# MCU_144_IOs_Clone.net
KiCad netlist of a schematic drawn in Altium Designer
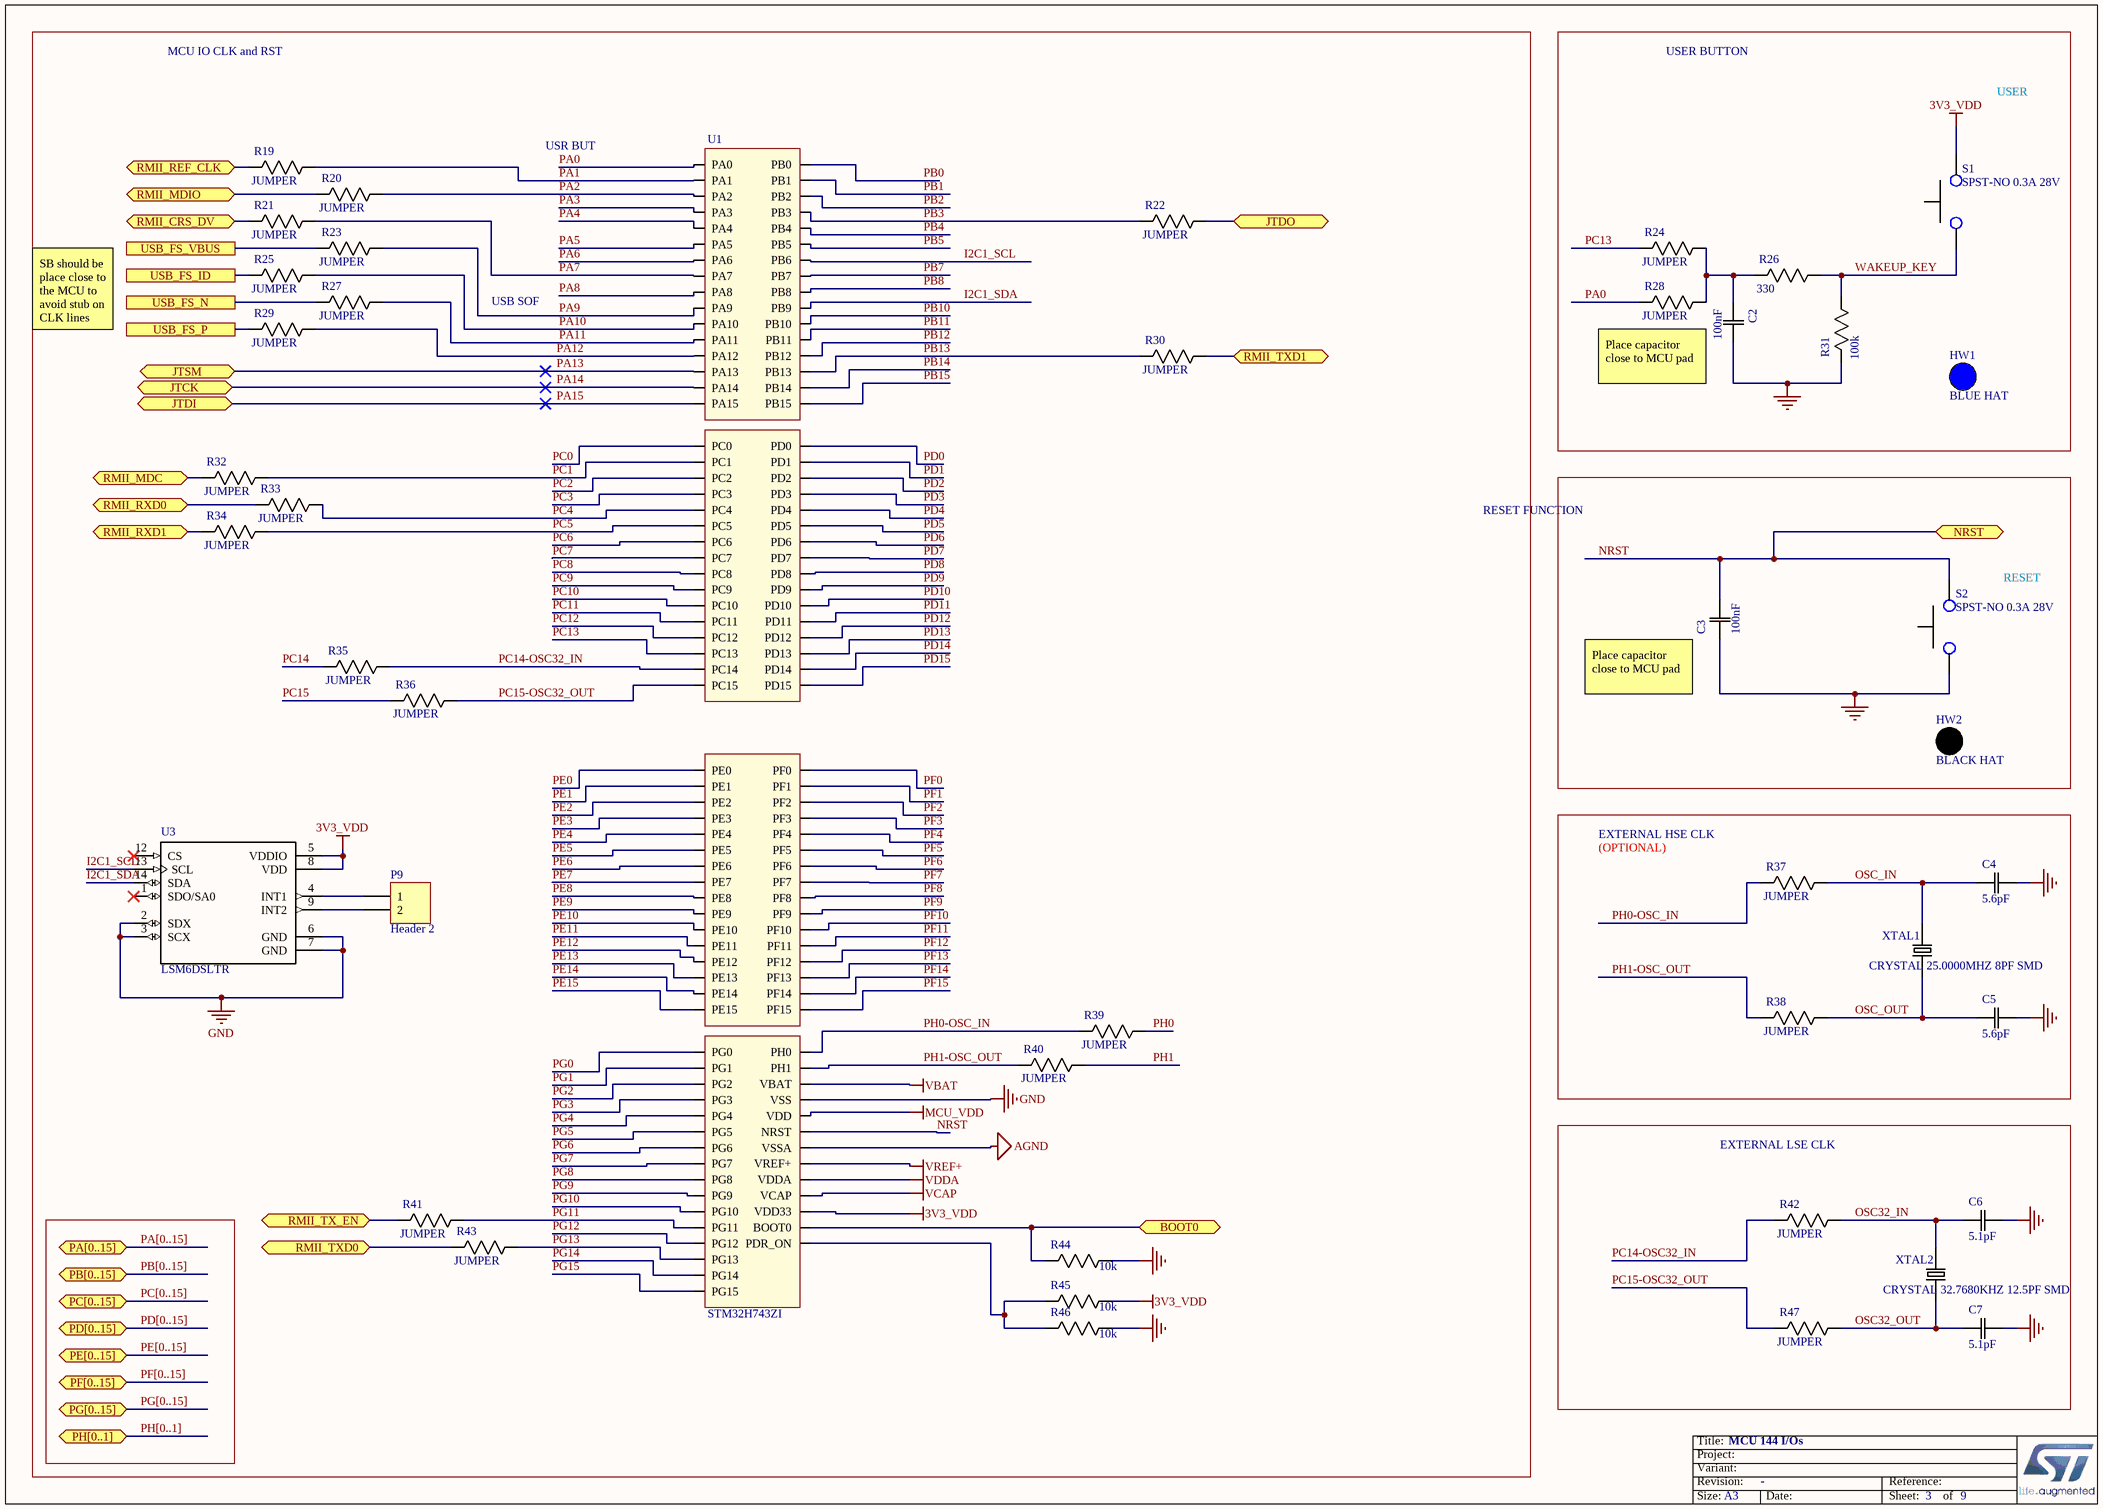
[diagram p0: MCU_144_IOs_Clone.SchDoc]

(export (version "E")
  (design (tool "Eeschema 10.0.6"))
  (components
    (comp (ref "C2")
      (value "100nF")
      (footprint "0805")
      (description "CAP CER 0.1UF 50V X7R 0805")
      (fields (field (name "MP") "CC0805KRX7R9BB104") (field (name "MF") "Yageo"))
      (libsource (lib "AltiumLibraries") (part "CAP 100nF 0805"))
    )
    (comp (ref "C3")
      (value "100nF")
      (footprint "0805")
      (description "CAP CER 0.1UF 50V X7R 0805")
      (fields (field (name "MP") "CC0805KRX7R9BB104") (field (name "MF") "Yageo"))
      (libsource (lib "AltiumLibraries") (part "CAP 100nF 0805"))
    )
    (comp (ref "C4")
      (value "5.6pF")
      (footprint "0805")
      (description "CAP CER 5.6PF 50V C0G/NP0 0805")
      (fields (field (name "MP") "C0805C569D5GACTU") (field (name "MF") "KEMET"))
      (libsource (lib "AltiumLibraries") (part "CAP 5.6pF 0805"))
    )
    (comp (ref "C5")
      (value "5.6pF")
      (footprint "0805")
      (description "CAP CER 5.6PF 50V C0G/NP0 0805")
      (fields (field (name "MP") "C0805C569D5GACTU") (field (name "MF") "KEMET"))
      (libsource (lib "AltiumLibraries") (part "CAP 5.6pF 0805"))
    )
    (comp (ref "C6")
      (value "5.1pF")
      (footprint "0805")
      (description "CAP CER 5.1PF 630V NP0 0805")
      (fields (field (name "MP") "C0805C519KBGAC7800") (field (name "MF") "KEMET"))
      (libsource (lib "AltiumLibraries") (part "CAP 5.1pF 0805"))
    )
    (comp (ref "C7")
      (value "5.1pF")
      (footprint "0805")
      (description "CAP CER 5.1PF 630V NP0 0805")
      (fields (field (name "MP") "C0805C519KBGAC7800") (field (name "MF") "KEMET"))
      (libsource (lib "AltiumLibraries") (part "CAP 5.1pF 0805"))
    )
    (comp (ref "HW1")
      (value "BLUE HAT")
      (description "Blue Hat for switch TD0341X-G01-BLU")
      (fields
        (field (name "INTERNAL_PART_NUMBER") "MCD-00634")
        (field (name "MANUFACTURER_PART_NUMBER") "988.16.09.3.00002_SH-517")
        (field (name "PROVIDED_BY") "SUBCO")
      )
      (libsource (lib "MCD_PARTS_database") (part "BUTTON_HAT_BLUE"))
    )
    (comp (ref "HW2")
      (value "BLACK HAT")
      (description "Black Hat for switch TD0341X-G01-BLA")
      (fields
        (field (name "INTERNAL_PART_NUMBER") "MCD-00635")
        (field (name "MANUFACTURER_PART_NUMBER") "988.16.09.3.00003_SH-517")
        (field (name "PROVIDED_BY") "SUBCO")
      )
      (libsource (lib "MCD_PARTS_database") (part "BUTTON_HAT_BLACK"))
    )
    (comp (ref "P9")
      (value "Header 2")
      (footprint "HDR1X2")
      (description "Header, 2-Pin")
      (fields (field (name "PUBLISHER") "Altium Limited"))
      (libsource (lib "Miscellaneous Connectors") (part "Header 2"))
    )
    (comp (ref "R19")
      (value "JUMPER")
      (footprint "0805")
      (description "RES SMD 0 OHM JUMPER 1/8W 0805")
      (fields (field (name "MP") "RC0805JR-070RL") (field (name "MF") "Yageo"))
      (libsource (lib "AltiumLibraries") (part "RES 0 0805"))
    )
    (comp (ref "R20")
      (value "JUMPER")
      (footprint "0805")
      (description "RES SMD 0 OHM JUMPER 1/8W 0805")
      (fields (field (name "MP") "RC0805JR-070RL") (field (name "MF") "Yageo"))
      (libsource (lib "AltiumLibraries") (part "RES 0 0805"))
    )
    (comp (ref "R21")
      (value "JUMPER")
      (footprint "0805")
      (description "RES SMD 0 OHM JUMPER 1/8W 0805")
      (fields (field (name "MP") "RC0805JR-070RL") (field (name "MF") "Yageo"))
      (libsource (lib "AltiumLibraries") (part "RES 0 0805"))
    )
    (comp (ref "R22")
      (value "JUMPER")
      (footprint "0805")
      (description "RES SMD 0 OHM JUMPER 1/8W 0805")
      (fields (field (name "MP") "RC0805JR-070RL") (field (name "MF") "Yageo"))
      (libsource (lib "AltiumLibraries") (part "RES 0 0805"))
    )
    (comp (ref "R23")
      (value "JUMPER")
      (footprint "0805")
      (description "RES SMD 0 OHM JUMPER 1/8W 0805")
      (fields (field (name "MP") "RC0805JR-070RL") (field (name "MF") "Yageo"))
      (libsource (lib "AltiumLibraries") (part "RES 0 0805"))
    )
    (comp (ref "R24")
      (value "JUMPER")
      (footprint "0805")
      (description "RES SMD 0 OHM JUMPER 1/8W 0805")
      (fields (field (name "MP") "RC0805JR-070RL") (field (name "MF") "Yageo"))
      (libsource (lib "AltiumLibraries") (part "RES 0 0805"))
    )
    (comp (ref "R25")
      (value "JUMPER")
      (footprint "0805")
      (description "RES SMD 0 OHM JUMPER 1/8W 0805")
      (fields (field (name "MP") "RC0805JR-070RL") (field (name "MF") "Yageo"))
      (libsource (lib "AltiumLibraries") (part "RES 0 0805"))
    )
    (comp (ref "R26")
      (value "330")
      (footprint "0805")
      (description "RES SMD 330 OHM 1% 1/8W 0805")
      (fields (field (name "MP") "RC0805FR-07330RL") (field (name "MF") "Yageo"))
      (libsource (lib "AltiumLibraries") (part "RES 330 0805"))
    )
    (comp (ref "R27")
      (value "JUMPER")
      (footprint "0805")
      (description "RES SMD 0 OHM JUMPER 1/8W 0805")
      (fields (field (name "MP") "RC0805JR-070RL") (field (name "MF") "Yageo"))
      (libsource (lib "AltiumLibraries") (part "RES 0 0805"))
    )
    (comp (ref "R28")
      (value "JUMPER")
      (footprint "0805")
      (description "RES SMD 0 OHM JUMPER 1/8W 0805")
      (fields (field (name "MP") "RC0805JR-070RL") (field (name "MF") "Yageo"))
      (libsource (lib "AltiumLibraries") (part "RES 0 0805"))
    )
    (comp (ref "R29")
      (value "JUMPER")
      (footprint "0805")
      (description "RES SMD 0 OHM JUMPER 1/8W 0805")
      (fields (field (name "MP") "RC0805JR-070RL") (field (name "MF") "Yageo"))
      (libsource (lib "AltiumLibraries") (part "RES 0 0805"))
    )
    (comp (ref "R30")
      (value "JUMPER")
      (footprint "0805")
      (description "RES SMD 0 OHM JUMPER 1/8W 0805")
      (fields (field (name "MP") "RC0805JR-070RL") (field (name "MF") "Yageo"))
      (libsource (lib "AltiumLibraries") (part "RES 0 0805"))
    )
    (comp (ref "R31")
      (value "100k")
      (footprint "0805")
      (description "RES SMD 100K OHM 1% 1/8W 0805")
      (fields (field (name "MP") "RC0805FR-07100KL") (field (name "MF") "Yageo"))
      (libsource (lib "AltiumLibraries") (part "RES 100k 0805"))
    )
    (comp (ref "R32")
      (value "JUMPER")
      (footprint "0805")
      (description "RES SMD 0 OHM JUMPER 1/8W 0805")
      (fields (field (name "MP") "RC0805JR-070RL") (field (name "MF") "Yageo"))
      (libsource (lib "AltiumLibraries") (part "RES 0 0805"))
    )
    (comp (ref "R33")
      (value "JUMPER")
      (footprint "0805")
      (description "RES SMD 0 OHM JUMPER 1/8W 0805")
      (fields (field (name "MP") "RC0805JR-070RL") (field (name "MF") "Yageo"))
      (libsource (lib "AltiumLibraries") (part "RES 0 0805"))
    )
    (comp (ref "R34")
      (value "JUMPER")
      (footprint "0805")
      (description "RES SMD 0 OHM JUMPER 1/8W 0805")
      (fields (field (name "MP") "RC0805JR-070RL") (field (name "MF") "Yageo"))
      (libsource (lib "AltiumLibraries") (part "RES 0 0805"))
    )
    (comp (ref "R35")
      (value "JUMPER")
      (footprint "0805")
      (description "RES SMD 0 OHM JUMPER 1/8W 0805")
      (fields (field (name "MP") "RC0805JR-070RL") (field (name "MF") "Yageo"))
      (libsource (lib "AltiumLibraries") (part "RES 0 0805"))
    )
    (comp (ref "R36")
      (value "JUMPER")
      (footprint "0805")
      (description "RES SMD 0 OHM JUMPER 1/8W 0805")
      (fields (field (name "MP") "RC0805JR-070RL") (field (name "MF") "Yageo"))
      (libsource (lib "AltiumLibraries") (part "RES 0 0805"))
    )
    (comp (ref "R37")
      (value "JUMPER")
      (footprint "0805")
      (description "RES SMD 0 OHM JUMPER 1/8W 0805")
      (fields (field (name "MP") "RC0805JR-070RL") (field (name "MF") "Yageo"))
      (libsource (lib "AltiumLibraries") (part "RES 0 0805"))
    )
    (comp (ref "R38")
      (value "JUMPER")
      (footprint "0805")
      (description "RES SMD 0 OHM JUMPER 1/8W 0805")
      (fields (field (name "MP") "RC0805JR-070RL") (field (name "MF") "Yageo"))
      (libsource (lib "AltiumLibraries") (part "RES 0 0805"))
    )
    (comp (ref "R39")
      (value "JUMPER")
      (footprint "0805")
      (description "RES SMD 0 OHM JUMPER 1/8W 0805")
      (fields (field (name "MP") "RC0805JR-070RL") (field (name "MF") "Yageo"))
      (libsource (lib "AltiumLibraries") (part "RES 0 0805"))
    )
    (comp (ref "R40")
      (value "JUMPER")
      (footprint "0805")
      (description "RES SMD 0 OHM JUMPER 1/8W 0805")
      (fields (field (name "MP") "RC0805JR-070RL") (field (name "MF") "Yageo"))
      (libsource (lib "AltiumLibraries") (part "RES 0 0805"))
    )
    (comp (ref "R41")
      (value "JUMPER")
      (footprint "0805")
      (description "RES SMD 0 OHM JUMPER 1/8W 0805")
      (fields (field (name "MP") "RC0805JR-070RL") (field (name "MF") "Yageo"))
      (libsource (lib "AltiumLibraries") (part "RES 0 0805"))
    )
    (comp (ref "R42")
      (value "JUMPER")
      (footprint "0805")
      (description "RES SMD 0 OHM JUMPER 1/8W 0805")
      (fields (field (name "MP") "RC0805JR-070RL") (field (name "MF") "Yageo"))
      (libsource (lib "AltiumLibraries") (part "RES 0 0805"))
    )
    (comp (ref "R43")
      (value "JUMPER")
      (footprint "0805")
      (description "RES SMD 0 OHM JUMPER 1/8W 0805")
      (fields (field (name "MP") "RC0805JR-070RL") (field (name "MF") "Yageo"))
      (libsource (lib "AltiumLibraries") (part "RES 0 0805"))
    )
    (comp (ref "R44")
      (value "10k")
      (footprint "0805")
      (description "RES SMD 10K OHM 1% 1/8W 0805")
      (fields (field (name "MP") "RC0805FR-0710KL") (field (name "MF") "Yageo"))
      (libsource (lib "") (part "RES 10k 0805_1"))
    )
    (comp (ref "R45")
      (value "10k")
      (footprint "0805")
      (description "RES SMD 10K OHM 1% 1/8W 0805")
      (fields (field (name "MP") "RC0805FR-0710KL") (field (name "MF") "Yageo"))
      (libsource (lib "AltiumLibraries") (part "RES 10k 0805"))
    )
    (comp (ref "R46")
      (value "10k")
      (footprint "0805")
      (description "RES SMD 10K OHM 1% 1/8W 0805")
      (fields (field (name "MP") "RC0805FR-0710KL") (field (name "MF") "Yageo"))
      (libsource (lib "AltiumLibraries") (part "RES 10k 0805"))
    )
    (comp (ref "R47")
      (value "JUMPER")
      (footprint "0805")
      (description "RES SMD 0 OHM JUMPER 1/8W 0805")
      (fields (field (name "MP") "RC0805JR-070RL") (field (name "MF") "Yageo"))
      (libsource (lib "AltiumLibraries") (part "RES 0 0805"))
    )
    (comp (ref "S1")
      (value "SPST-NO 0.3A 28V")
      (footprint "PB300STQ")
      (description "Pushbutton Switch SPST-NO Standard Through Hole")
      (fields (field (name "MF") "E-Switch") (field (name "MP") "PB300STQ"))
      (libsource (lib "AltiumLibraries") (part "SW PUSH NO"))
    )
    (comp (ref "S2")
      (value "SPST-NO 0.3A 28V")
      (footprint "PB300STQ")
      (description "Pushbutton Switch SPST-NO Standard Through Hole")
      (fields (field (name "MF") "E-Switch") (field (name "MP") "PB300STQ"))
      (libsource (lib "AltiumLibraries") (part "SW PUSH NO"))
    )
    (comp (ref "U1")
      (value "STM32H743ZI")
      (footprint "STM32H7")
      (fields (field (name "MF") "STMicroelectronics") (field (name "MP") "STM32H743ZIT6"))
      (libsource (lib "AltiumLibraries") (part "STM32H743ZI"))
    )
    (comp (ref "U3")
      (value "LSM6DSLTR")
      (footprint "LGA-14")
      (description "Accelerometer, Gyroscope, Temperature, 6 Axis Sensor IÂ²C, SPI Output")
      (fields (field (name "MF") "STMicroelectronics"))
      (libsource (lib "AltiumLibraries") (part "LSM6DSLTR"))
    )
    (comp (ref "XTAL1")
      (value "CRYSTAL 25.0000MHZ 8PF SMD")
      (footprint "SMD-2")
      (description "25MHz ±50ppm Crystal 8pF 70 Ohms 2-SMD, No Lead")
      (fields (field (name "MP") "NX5032GA-25.000000MHZ-LN-CD-1") (field (name "MF") "NDK America, Inc."))
      (libsource (lib "AltiumLibraries") (part "XTAL 25MHZ 8PF SMD"))
    )
    (comp (ref "XTAL2")
      (value "CRYSTAL 32.7680KHZ 12.5PF SMD")
      (footprint "SMD-2")
      (description "32.768kHz ±20ppm Crystal 12.5pF 70 kOhms 2-SMD, No Lead")
      (fields (field (name "MP") "NX3215SA-32.768K-STD-MUA-8") (field (name "MF") "NDK America, Inc."))
      (libsource (lib "AltiumLibraries") (part "XTAL 32.7680KHZ 12.5PF SMD"))
    )
  )
  (nets
    (net (code "3") (name "/BOOT0") (class "Default")
      (node (ref "R44") (pin "2") (pinfunction "R2_2") (pintype "passive"))
      (node (ref "U1") (pin "BOOT0") (pinfunction "BOOT0_BOOT0") (pintype "passive"))
    )
    (net (code "4") (name "/I2C1_SCL") (class "Default")
      (node (ref "U1") (pin "PB6") (pinfunction "PB6_PB6") (pintype "passive"))
      (node (ref "U3") (pin "13") (pinfunction "SCL_13") (pintype "input"))
    )
    (net (code "5") (name "/I2C1_SDA") (class "Default")
      (node (ref "U1") (pin "PB9") (pinfunction "PB9_PB9") (pintype "passive"))
      (node (ref "U3") (pin "14") (pinfunction "SDA_14") (pintype "bidirectional"))
    )
    (net (code "6") (name "/JTDO") (class "Default")
      (node (ref "R22") (pin "1") (pinfunction "R1_1") (pintype "passive"))
    )
    (net (code "7") (name "/NRST") (class "Default")
      (node (ref "C3") (pin "2") (pinfunction "C2_2") (pintype "passive"))
      (node (ref "S2") (pin "2") (pinfunction "2_2") (pintype "passive"))
      (node (ref "U1") (pin "NRST") (pinfunction "NRST_NRST") (pintype "passive"))
    )
    (net (code "8") (name "/OSC32_IN") (class "Default")
      (node (ref "C6") (pin "1") (pinfunction "C1_1") (pintype "passive"))
      (node (ref "R42") (pin "1") (pinfunction "R1_1") (pintype "passive"))
      (node (ref "XTAL2") (pin "2") (pinfunction "2_2") (pintype "passive"))
    )
    (net (code "9") (name "/OSC32_OUT") (class "Default")
      (node (ref "C7") (pin "1") (pinfunction "C1_1") (pintype "passive"))
      (node (ref "R47") (pin "1") (pinfunction "R1_1") (pintype "passive"))
      (node (ref "XTAL2") (pin "1") (pinfunction "1_1") (pintype "passive"))
    )
    (net (code "10") (name "/OSC_IN") (class "Default")
      (node (ref "C4") (pin "1") (pinfunction "C1_1") (pintype "passive"))
      (node (ref "R37") (pin "1") (pinfunction "R1_1") (pintype "passive"))
      (node (ref "XTAL1") (pin "2") (pinfunction "2_2") (pintype "passive"))
    )
    (net (code "11") (name "/OSC_OUT") (class "Default")
      (node (ref "C5") (pin "1") (pinfunction "C1_1") (pintype "passive"))
      (node (ref "R38") (pin "1") (pinfunction "R1_1") (pintype "passive"))
      (node (ref "XTAL1") (pin "1") (pinfunction "1_1") (pintype "passive"))
    )
    (net (code "12") (name "/PA0") (class "Default")
      (node (ref "R28") (pin "2") (pinfunction "R2_2") (pintype "passive"))
      (node (ref "U1") (pin "PA0") (pinfunction "PA0_PA0") (pintype "passive"))
    )
    (net (code "13") (name "/PA1") (class "Default")
      (node (ref "R19") (pin "1") (pinfunction "R1_1") (pintype "passive"))
      (node (ref "U1") (pin "PA1") (pinfunction "PA1_PA1") (pintype "passive"))
    )
    (net (code "14") (name "/PA2") (class "Default")
      (node (ref "R20") (pin "1") (pinfunction "R1_1") (pintype "passive"))
      (node (ref "U1") (pin "PA2") (pinfunction "PA2_PA2") (pintype "passive"))
    )
    (net (code "15") (name "/PA3") (class "Default")
      (node (ref "U1") (pin "PA3") (pinfunction "PA3_PA3") (pintype "passive"))
    )
    (net (code "16") (name "/PA4") (class "Default")
      (node (ref "U1") (pin "PA4") (pinfunction "PA4_PA4") (pintype "passive"))
    )
    (net (code "17") (name "/PA5") (class "Default")
      (node (ref "U1") (pin "PA5") (pinfunction "PA5_PA5") (pintype "passive"))
    )
    (net (code "18") (name "/PA6") (class "Default")
      (node (ref "U1") (pin "PA6") (pinfunction "PA6_PA6") (pintype "passive"))
    )
    (net (code "19") (name "/PA7") (class "Default")
      (node (ref "R21") (pin "1") (pinfunction "R1_1") (pintype "passive"))
      (node (ref "U1") (pin "PA7") (pinfunction "PA7_PA7") (pintype "passive"))
    )
    (net (code "20") (name "/PA8") (class "Default")
      (node (ref "U1") (pin "PA8") (pinfunction "PA8_PA8") (pintype "passive"))
    )
    (net (code "21") (name "/PA9") (class "Default")
      (node (ref "R23") (pin "1") (pinfunction "R1_1") (pintype "passive"))
      (node (ref "U1") (pin "PA9") (pinfunction "PA9_PA9") (pintype "passive"))
    )
    (net (code "22") (name "/PA10") (class "Default")
      (node (ref "R25") (pin "1") (pinfunction "R1_1") (pintype "passive"))
      (node (ref "U1") (pin "PA10") (pinfunction "PA10_PA10") (pintype "passive"))
    )
    (net (code "23") (name "/PA11") (class "Default")
      (node (ref "R27") (pin "1") (pinfunction "R1_1") (pintype "passive"))
      (node (ref "U1") (pin "PA11") (pinfunction "PA11_PA11") (pintype "passive"))
    )
    (net (code "24") (name "/PA12") (class "Default")
      (node (ref "R29") (pin "1") (pinfunction "R1_1") (pintype "passive"))
      (node (ref "U1") (pin "PA12") (pinfunction "PA12_PA12") (pintype "passive"))
    )
    (net (code "25") (name "/PA13") (class "Default")
      (node (ref "U1") (pin "PA13") (pinfunction "PA13_PA13") (pintype "passive"))
    )
    (net (code "26") (name "/PA14") (class "Default")
      (node (ref "U1") (pin "PA14") (pinfunction "PA14_PA14") (pintype "passive"))
    )
    (net (code "27") (name "/PA15") (class "Default")
      (node (ref "U1") (pin "PA15") (pinfunction "PA15_PA15") (pintype "passive"))
    )
    (net (code "29") (name "/PB0") (class "Default")
      (node (ref "U1") (pin "PB0") (pinfunction "PB0_PB0") (pintype "passive"))
    )
    (net (code "30") (name "/PB1") (class "Default")
      (node (ref "U1") (pin "PB1") (pinfunction "PB1_PB1") (pintype "passive"))
    )
    (net (code "31") (name "/PB2") (class "Default")
      (node (ref "U1") (pin "PB2") (pinfunction "PB2_PB2") (pintype "passive"))
    )
    (net (code "32") (name "/PB3") (class "Default")
      (node (ref "R22") (pin "2") (pinfunction "R2_2") (pintype "passive"))
      (node (ref "U1") (pin "PB3") (pinfunction "PB3_PB3") (pintype "passive"))
    )
    (net (code "33") (name "/PB4") (class "Default")
      (node (ref "U1") (pin "PB4") (pinfunction "PB4_PB4") (pintype "passive"))
    )
    (net (code "34") (name "/PB5") (class "Default")
      (node (ref "U1") (pin "PB5") (pinfunction "PB5_PB5") (pintype "passive"))
    )
    (net (code "35") (name "/PB7") (class "Default")
      (node (ref "U1") (pin "PB7") (pinfunction "PB7_PB7") (pintype "passive"))
    )
    (net (code "36") (name "/PB8") (class "Default")
      (node (ref "U1") (pin "PB8") (pinfunction "PB8_PB8") (pintype "passive"))
    )
    (net (code "37") (name "/PB10") (class "Default")
      (node (ref "U1") (pin "PB10") (pinfunction "PB10_PB10") (pintype "passive"))
    )
    (net (code "38") (name "/PB11") (class "Default")
      (node (ref "U1") (pin "PB11") (pinfunction "PB11_PB11") (pintype "passive"))
    )
    (net (code "39") (name "/PB12") (class "Default")
      (node (ref "U1") (pin "PB12") (pinfunction "PB12_PB12") (pintype "passive"))
    )
    (net (code "40") (name "/PB13") (class "Default")
      (node (ref "R30") (pin "2") (pinfunction "R2_2") (pintype "passive"))
      (node (ref "U1") (pin "PB13") (pinfunction "PB13_PB13") (pintype "passive"))
    )
    (net (code "41") (name "/PB14") (class "Default")
      (node (ref "U1") (pin "PB14") (pinfunction "PB14_PB14") (pintype "passive"))
    )
    (net (code "42") (name "/PB15") (class "Default")
      (node (ref "U1") (pin "PB15") (pinfunction "PB15_PB15") (pintype "passive"))
    )
    (net (code "44") (name "/PC0") (class "Default")
      (node (ref "U1") (pin "PC0") (pinfunction "PC0_PC0") (pintype "passive"))
    )
    (net (code "45") (name "/PC1") (class "Default")
      (node (ref "R32") (pin "1") (pinfunction "R1_1") (pintype "passive"))
      (node (ref "U1") (pin "PC1") (pinfunction "PC1_PC1") (pintype "passive"))
    )
    (net (code "46") (name "/PC2") (class "Default")
      (node (ref "U1") (pin "PC2") (pinfunction "PC2_PC2") (pintype "passive"))
    )
    (net (code "47") (name "/PC3") (class "Default")
      (node (ref "U1") (pin "PC3") (pinfunction "PC3_PC3") (pintype "passive"))
    )
    (net (code "48") (name "/PC4") (class "Default")
      (node (ref "R33") (pin "1") (pinfunction "R1_1") (pintype "passive"))
      (node (ref "U1") (pin "PC4") (pinfunction "PC4_PC4") (pintype "passive"))
    )
    (net (code "49") (name "/PC5") (class "Default")
      (node (ref "R34") (pin "1") (pinfunction "R1_1") (pintype "passive"))
      (node (ref "U1") (pin "PC5") (pinfunction "PC5_PC5") (pintype "passive"))
    )
    (net (code "50") (name "/PC6") (class "Default")
      (node (ref "U1") (pin "PC6") (pinfunction "PC6_PC6") (pintype "passive"))
    )
    (net (code "51") (name "/PC7") (class "Default")
      (node (ref "U1") (pin "PC7") (pinfunction "PC7_PC7") (pintype "passive"))
    )
    (net (code "52") (name "/PC8") (class "Default")
      (node (ref "U1") (pin "PC8") (pinfunction "PC8_PC8") (pintype "passive"))
    )
    (net (code "53") (name "/PC9") (class "Default")
      (node (ref "U1") (pin "PC9") (pinfunction "PC9_PC9") (pintype "passive"))
    )
    (net (code "54") (name "/PC10") (class "Default")
      (node (ref "U1") (pin "PC10") (pinfunction "PC10_PC10") (pintype "passive"))
    )
    (net (code "55") (name "/PC11") (class "Default")
      (node (ref "U1") (pin "PC11") (pinfunction "PC11_PC11") (pintype "passive"))
    )
    (net (code "56") (name "/PC12") (class "Default")
      (node (ref "U1") (pin "PC12") (pinfunction "PC12_PC12") (pintype "passive"))
    )
    (net (code "57") (name "/PC13") (class "Default")
      (node (ref "R24") (pin "2") (pinfunction "R2_2") (pintype "passive"))
      (node (ref "U1") (pin "PC13") (pinfunction "PC13_PC13") (pintype "passive"))
    )
    (net (code "58") (name "/PC14") (class "Default")
      (node (ref "R35") (pin "2") (pinfunction "R2_2") (pintype "passive"))
    )
    (net (code "59") (name "/PC14-OSC32_IN") (class "Default")
      (node (ref "R35") (pin "1") (pinfunction "R1_1") (pintype "passive"))
      (node (ref "R42") (pin "2") (pinfunction "R2_2") (pintype "passive"))
      (node (ref "U1") (pin "PC14") (pinfunction "PC14_PC14") (pintype "passive"))
    )
    (net (code "60") (name "/PC15") (class "Default")
      (node (ref "R36") (pin "2") (pinfunction "R2_2") (pintype "passive"))
    )
    (net (code "61") (name "/PC15-OSC32_OUT") (class "Default")
      (node (ref "R36") (pin "1") (pinfunction "R1_1") (pintype "passive"))
      (node (ref "R47") (pin "2") (pinfunction "R2_2") (pintype "passive"))
      (node (ref "U1") (pin "PC15") (pinfunction "PC15_PC15") (pintype "passive"))
    )
    (net (code "63") (name "/PD0") (class "Default")
      (node (ref "U1") (pin "PD0") (pinfunction "PD0_PD0") (pintype "passive"))
    )
    (net (code "64") (name "/PD1") (class "Default")
      (node (ref "U1") (pin "PD1") (pinfunction "PD1_PD1") (pintype "passive"))
    )
    (net (code "65") (name "/PD2") (class "Default")
      (node (ref "U1") (pin "PD2") (pinfunction "PD2_PD2") (pintype "passive"))
    )
    (net (code "66") (name "/PD3") (class "Default")
      (node (ref "U1") (pin "PD3") (pinfunction "PD3_PD3") (pintype "passive"))
    )
    (net (code "67") (name "/PD4") (class "Default")
      (node (ref "U1") (pin "PD4") (pinfunction "PD4_PD4") (pintype "passive"))
    )
    (net (code "68") (name "/PD5") (class "Default")
      (node (ref "U1") (pin "PD5") (pinfunction "PD5_PD5") (pintype "passive"))
    )
    (net (code "69") (name "/PD6") (class "Default")
      (node (ref "U1") (pin "PD6") (pinfunction "PD6_PD6") (pintype "passive"))
    )
    (net (code "70") (name "/PD7") (class "Default")
      (node (ref "U1") (pin "PD7") (pinfunction "PD7_PD7") (pintype "passive"))
    )
    (net (code "71") (name "/PD8") (class "Default")
      (node (ref "U1") (pin "PD8") (pinfunction "PD8_PD8") (pintype "passive"))
    )
    (net (code "72") (name "/PD9") (class "Default")
      (node (ref "U1") (pin "PD9") (pinfunction "PD9_PD9") (pintype "passive"))
    )
    (net (code "73") (name "/PD10") (class "Default")
      (node (ref "U1") (pin "PD10") (pinfunction "PD10_PD10") (pintype "passive"))
    )
    (net (code "74") (name "/PD11") (class "Default")
      (node (ref "U1") (pin "PD11") (pinfunction "PD11_PD11") (pintype "passive"))
    )
    (net (code "75") (name "/PD12") (class "Default")
      (node (ref "U1") (pin "PD12") (pinfunction "PD12_PD12") (pintype "passive"))
    )
    (net (code "76") (name "/PD13") (class "Default")
      (node (ref "U1") (pin "PD13") (pinfunction "PD13_PD13") (pintype "passive"))
    )
    (net (code "77") (name "/PD14") (class "Default")
      (node (ref "U1") (pin "PD14") (pinfunction "PD14_PD14") (pintype "passive"))
    )
    (net (code "78") (name "/PD15") (class "Default")
      (node (ref "U1") (pin "PD15") (pinfunction "PD15_PD15") (pintype "passive"))
    )
    (net (code "80") (name "/PE0") (class "Default")
      (node (ref "U1") (pin "PE0") (pinfunction "PE0_PE0") (pintype "passive"))
    )
    (net (code "81") (name "/PE1") (class "Default")
      (node (ref "U1") (pin "PE1") (pinfunction "PE1_PE1") (pintype "passive"))
    )
    (net (code "82") (name "/PE2") (class "Default")
      (node (ref "U1") (pin "PE2") (pinfunction "PE2_PE2") (pintype "passive"))
    )
    (net (code "83") (name "/PE3") (class "Default")
      (node (ref "U1") (pin "PE3") (pinfunction "PE3_PE3") (pintype "passive"))
    )
    (net (code "84") (name "/PE4") (class "Default")
      (node (ref "U1") (pin "PE4") (pinfunction "PE4_PE4") (pintype "passive"))
    )
    (net (code "85") (name "/PE5") (class "Default")
      (node (ref "U1") (pin "PE5") (pinfunction "PE5_PE5") (pintype "passive"))
    )
    (net (code "86") (name "/PE6") (class "Default")
      (node (ref "U1") (pin "PE6") (pinfunction "PE6_PE6") (pintype "passive"))
    )
    (net (code "87") (name "/PE7") (class "Default")
      (node (ref "U1") (pin "PE7") (pinfunction "PE7_PE7") (pintype "passive"))
    )
    (net (code "88") (name "/PE8") (class "Default")
      (node (ref "U1") (pin "PE8") (pinfunction "PE8_PE8") (pintype "passive"))
    )
    (net (code "89") (name "/PE9") (class "Default")
      (node (ref "U1") (pin "PE9") (pinfunction "PE9_PE9") (pintype "passive"))
    )
    (net (code "90") (name "/PE10") (class "Default")
      (node (ref "U1") (pin "PE10") (pinfunction "PE10_PE10") (pintype "passive"))
    )
    (net (code "91") (name "/PE11") (class "Default")
      (node (ref "U1") (pin "PE11") (pinfunction "PE11_PE11") (pintype "passive"))
    )
    (net (code "92") (name "/PE12") (class "Default")
      (node (ref "U1") (pin "PE12") (pinfunction "PE12_PE12") (pintype "passive"))
    )
    (net (code "93") (name "/PE13") (class "Default")
      (node (ref "U1") (pin "PE13") (pinfunction "PE13_PE13") (pintype "passive"))
    )
    (net (code "94") (name "/PE14") (class "Default")
      (node (ref "U1") (pin "PE14") (pinfunction "PE14_PE14") (pintype "passive"))
    )
    (net (code "95") (name "/PE15") (class "Default")
      (node (ref "U1") (pin "PE15") (pinfunction "PE15_PE15") (pintype "passive"))
    )
    (net (code "97") (name "/PF0") (class "Default")
      (node (ref "U1") (pin "PF0") (pinfunction "PF0_PF0") (pintype "passive"))
    )
    (net (code "98") (name "/PF1") (class "Default")
      (node (ref "U1") (pin "PF1") (pinfunction "PF1_PF1") (pintype "passive"))
    )
    (net (code "99") (name "/PF2") (class "Default")
      (node (ref "U1") (pin "PF2") (pinfunction "PF2_PF2") (pintype "passive"))
    )
    (net (code "100") (name "/PF3") (class "Default")
      (node (ref "U1") (pin "PF3") (pinfunction "PF3_PF3") (pintype "passive"))
    )
    (net (code "101") (name "/PF4") (class "Default")
      (node (ref "U1") (pin "PF4") (pinfunction "PF4_PF4") (pintype "passive"))
    )
    (net (code "102") (name "/PF5") (class "Default")
      (node (ref "U1") (pin "PF5") (pinfunction "PF5_PF5") (pintype "passive"))
    )
    (net (code "103") (name "/PF6") (class "Default")
      (node (ref "U1") (pin "PF6") (pinfunction "PF6_PF6") (pintype "passive"))
    )
    (net (code "104") (name "/PF7") (class "Default")
      (node (ref "U1") (pin "PF7") (pinfunction "PF7_PF7") (pintype "passive"))
    )
    (net (code "105") (name "/PF8") (class "Default")
      (node (ref "U1") (pin "PF8") (pinfunction "PF8_PF8") (pintype "passive"))
    )
    (net (code "106") (name "/PF9") (class "Default")
      (node (ref "U1") (pin "PF9") (pinfunction "PF9_PF9") (pintype "passive"))
    )
    (net (code "107") (name "/PF10") (class "Default")
      (node (ref "U1") (pin "PF10") (pinfunction "PF10_PF10") (pintype "passive"))
    )
    (net (code "108") (name "/PF11") (class "Default")
      (node (ref "U1") (pin "PF11") (pinfunction "PF11_PF11") (pintype "passive"))
    )
    (net (code "109") (name "/PF12") (class "Default")
      (node (ref "U1") (pin "PF12") (pinfunction "PF12_PF12") (pintype "passive"))
    )
    (net (code "110") (name "/PF13") (class "Default")
      (node (ref "U1") (pin "PF13") (pinfunction "PF13_PF13") (pintype "passive"))
    )
    (net (code "111") (name "/PF14") (class "Default")
      (node (ref "U1") (pin "PF14") (pinfunction "PF14_PF14") (pintype "passive"))
    )
    (net (code "112") (name "/PF15") (class "Default")
      (node (ref "U1") (pin "PF15") (pinfunction "PF15_PF15") (pintype "passive"))
    )
    (net (code "114") (name "/PG0") (class "Default")
      (node (ref "U1") (pin "PG0") (pinfunction "PG0_PG0") (pintype "passive"))
    )
    (net (code "115") (name "/PG1") (class "Default")
      (node (ref "U1") (pin "PG1") (pinfunction "PG1_PG1") (pintype "passive"))
    )
    (net (code "116") (name "/PG2") (class "Default")
      (node (ref "U1") (pin "PG2") (pinfunction "PG2_PG2") (pintype "passive"))
    )
    (net (code "117") (name "/PG3") (class "Default")
      (node (ref "U1") (pin "PG3") (pinfunction "PG3_PG3") (pintype "passive"))
    )
    (net (code "118") (name "/PG4") (class "Default")
      (node (ref "U1") (pin "PG4") (pinfunction "PG4_PG4") (pintype "passive"))
    )
    (net (code "119") (name "/PG5") (class "Default")
      (node (ref "U1") (pin "PG5") (pinfunction "PG5_PG5") (pintype "passive"))
    )
    (net (code "120") (name "/PG6") (class "Default")
      (node (ref "U1") (pin "PG6") (pinfunction "PG6_PG6") (pintype "passive"))
    )
    (net (code "121") (name "/PG7") (class "Default")
      (node (ref "U1") (pin "PG7") (pinfunction "PG7_PG7") (pintype "passive"))
    )
    (net (code "122") (name "/PG8") (class "Default")
      (node (ref "U1") (pin "PG8") (pinfunction "PG8_PG8") (pintype "passive"))
    )
    (net (code "123") (name "/PG9") (class "Default")
      (node (ref "U1") (pin "PG9") (pinfunction "PG9_PG9") (pintype "passive"))
    )
    (net (code "124") (name "/PG10") (class "Default")
      (node (ref "U1") (pin "PG10") (pinfunction "PG10_PG10") (pintype "passive"))
    )
    (net (code "125") (name "/PG11") (class "Default")
      (node (ref "R41") (pin "1") (pinfunction "R1_1") (pintype "passive"))
      (node (ref "U1") (pin "PG11") (pinfunction "PG11_PG11") (pintype "passive"))
    )
    (net (code "126") (name "/PG12") (class "Default")
      (node (ref "U1") (pin "PG12") (pinfunction "PG12_PG12") (pintype "passive"))
    )
    (net (code "127") (name "/PG13") (class "Default")
      (node (ref "R43") (pin "1") (pinfunction "R1_1") (pintype "passive"))
      (node (ref "U1") (pin "PG13") (pinfunction "PG13_PG13") (pintype "passive"))
    )
    (net (code "128") (name "/PG14") (class "Default")
      (node (ref "U1") (pin "PG14") (pinfunction "PG14_PG14") (pintype "passive"))
    )
    (net (code "129") (name "/PG15") (class "Default")
      (node (ref "U1") (pin "PG15") (pinfunction "PG15_PG15") (pintype "passive"))
    )
    (net (code "131") (name "/PH0") (class "Default")
      (node (ref "R39") (pin "1") (pinfunction "R1_1") (pintype "passive"))
    )
    (net (code "132") (name "/PH0-OSC_IN") (class "Default")
      (node (ref "R37") (pin "2") (pinfunction "R2_2") (pintype "passive"))
      (node (ref "R39") (pin "2") (pinfunction "R2_2") (pintype "passive"))
      (node (ref "U1") (pin "PH0") (pinfunction "PH0_PH0") (pintype "passive"))
    )
    (net (code "133") (name "/PH1") (class "Default")
      (node (ref "R40") (pin "1") (pinfunction "R1_1") (pintype "passive"))
    )
    (net (code "134") (name "/PH1-OSC_OUT") (class "Default")
      (node (ref "R38") (pin "2") (pinfunction "R2_2") (pintype "passive"))
      (node (ref "R40") (pin "2") (pinfunction "R2_2") (pintype "passive"))
      (node (ref "U1") (pin "PH1") (pinfunction "PH1_PH1") (pintype "passive"))
    )
    (net (code "136") (name "/RMII_CRS_DV") (class "Default")
      (node (ref "R21") (pin "2") (pinfunction "R2_2") (pintype "passive"))
    )
    (net (code "137") (name "/RMII_MDC") (class "Default")
      (node (ref "R32") (pin "2") (pinfunction "R2_2") (pintype "passive"))
    )
    (net (code "138") (name "/RMII_MDIO") (class "Default")
      (node (ref "R20") (pin "2") (pinfunction "R2_2") (pintype "passive"))
    )
    (net (code "139") (name "/RMII_REF_CLK") (class "Default")
      (node (ref "R19") (pin "2") (pinfunction "R2_2") (pintype "passive"))
    )
    (net (code "140") (name "/RMII_RXD0") (class "Default")
      (node (ref "R33") (pin "2") (pinfunction "R2_2") (pintype "passive"))
    )
    (net (code "141") (name "/RMII_RXD1") (class "Default")
      (node (ref "R34") (pin "2") (pinfunction "R2_2") (pintype "passive"))
    )
    (net (code "142") (name "/RMII_TXD0") (class "Default")
      (node (ref "R43") (pin "2") (pinfunction "R2_2") (pintype "passive"))
    )
    (net (code "143") (name "/RMII_TXD1") (class "Default")
      (node (ref "R30") (pin "1") (pinfunction "R1_1") (pintype "passive"))
    )
    (net (code "144") (name "/RMII_TX_EN") (class "Default")
      (node (ref "R41") (pin "2") (pinfunction "R2_2") (pintype "passive"))
    )
    (net (code "145") (name "/USB_FS_ID") (class "Default")
      (node (ref "R25") (pin "2") (pinfunction "R2_2") (pintype "passive"))
    )
    (net (code "146") (name "/USB_FS_N") (class "Default")
      (node (ref "R27") (pin "2") (pinfunction "R2_2") (pintype "passive"))
    )
    (net (code "147") (name "/USB_FS_P") (class "Default")
      (node (ref "R29") (pin "2") (pinfunction "R2_2") (pintype "passive"))
    )
    (net (code "148") (name "/USB_FS_VBUS") (class "Default")
      (node (ref "R23") (pin "2") (pinfunction "R2_2") (pintype "passive"))
    )
    (net (code "149") (name "/WAKEUP_KEY") (class "Default")
      (node (ref "R26") (pin "1") (pinfunction "R1_1") (pintype "passive"))
      (node (ref "R31") (pin "1") (pinfunction "R1_1") (pintype "passive"))
      (node (ref "S1") (pin "1") (pinfunction "1_1") (pintype "passive"))
    )
    (net (code "150") (name "3V3_VDD") (class "Default")
      (node (ref "R45") (pin "1") (pinfunction "R1_1") (pintype "passive"))
      (node (ref "S1") (pin "2") (pinfunction "2_2") (pintype "passive"))
      (node (ref "U1") (pin "VDD33USB") (pinfunction "VDD33_VDD33USB") (pintype "passive"))
      (node (ref "U3") (pin "5") (pinfunction "VDDIO_5") (pintype "power_in"))
      (node (ref "U3") (pin "8") (pinfunction "VDD_8") (pintype "power_in"))
    )
    (net (code "151") (name "AGND") (class "Default")
      (node (ref "U1") (pin "VSSA") (pinfunction "VSSA_VSSA") (pintype "passive"))
    )
    (net (code "152") (name "GND") (class "Default")
      (node (ref "C2") (pin "2") (pinfunction "C2_2") (pintype "passive"))
      (node (ref "C3") (pin "1") (pinfunction "C1_1") (pintype "passive"))
      (node (ref "C4") (pin "2") (pinfunction "C2_2") (pintype "passive"))
      (node (ref "C5") (pin "2") (pinfunction "C2_2") (pintype "passive"))
      (node (ref "C6") (pin "2") (pinfunction "C2_2") (pintype "passive"))
      (node (ref "C7") (pin "2") (pinfunction "C2_2") (pintype "passive"))
      (node (ref "R31") (pin "2") (pinfunction "R2_2") (pintype "passive"))
      (node (ref "R44") (pin "1") (pinfunction "R1_1") (pintype "passive"))
      (node (ref "R46") (pin "1") (pinfunction "R1_1") (pintype "passive"))
      (node (ref "S2") (pin "1") (pinfunction "1_1") (pintype "passive"))
      (node (ref "U1") (pin "VSS") (pinfunction "VSS_VSS") (pintype "passive"))
      (node (ref "U3") (pin "2") (pinfunction "SDX_2") (pintype "bidirectional"))
      (node (ref "U3") (pin "3") (pinfunction "SCX_3") (pintype "bidirectional"))
      (node (ref "U3") (pin "6") (pinfunction "GND_6") (pintype "power_in"))
      (node (ref "U3") (pin "7") (pinfunction "GND_7") (pintype "power_in"))
    )
    (net (code "153") (name "MCU_VDD") (class "Default")
      (node (ref "U1") (pin "VDD") (pinfunction "VDD_VDD") (pintype "passive"))
    )
    (net (code "154") (name "Net-(C2-C1)") (class "Default")
      (node (ref "C2") (pin "1") (pinfunction "C1_1") (pintype "passive"))
      (node (ref "R24") (pin "1") (pinfunction "R1_1") (pintype "passive"))
      (node (ref "R26") (pin "2") (pinfunction "R2_2") (pintype "passive"))
      (node (ref "R28") (pin "1") (pinfunction "R1_1") (pintype "passive"))
    )
    (net (code "155") (name "Net-(R45-R2)") (class "Default")
      (node (ref "R45") (pin "2") (pinfunction "R2_2") (pintype "passive"))
      (node (ref "R46") (pin "2") (pinfunction "R2_2") (pintype "passive"))
      (node (ref "U1") (pin "PDR_ON") (pinfunction "PDR_ON_PDR_ON") (pintype "passive"))
    )
    (net (code "156") (name "Net-(U3-INT1)") (class "Default")
      (node (ref "P9") (pin "1") (pinfunction "1_1") (pintype "passive"))
      (node (ref "U3") (pin "4") (pinfunction "INT1_4") (pintype "output"))
    )
    (net (code "157") (name "Net-(U3-INT2)") (class "Default")
      (node (ref "P9") (pin "2") (pinfunction "2_2") (pintype "passive"))
      (node (ref "U3") (pin "9") (pinfunction "INT2_9") (pintype "output"))
    )
    (net (code "158") (name "VBAT") (class "Default")
      (node (ref "U1") (pin "VBAT") (pinfunction "VBAT_VBAT") (pintype "passive"))
    )
    (net (code "159") (name "VCAP") (class "Default")
      (node (ref "U1") (pin "VCAP") (pinfunction "VCAP_VCAP") (pintype "passive"))
    )
    (net (code "160") (name "VDDA") (class "Default")
      (node (ref "U1") (pin "VDDA") (pinfunction "VDDA_VDDA") (pintype "passive"))
    )
    (net (code "161") (name "VREF+") (class "Default")
      (node (ref "U1") (pin "VREF+") (pinfunction "VREF+_VREF+") (pintype "passive"))
    )
    (net (code "162") (name "unconnected-(U3-CS-Pad12)") (class "Default")
      (node (ref "U3") (pin "12") (pinfunction "CS_12") (pintype "input+no_connect"))
    )
    (net (code "163") (name "unconnected-(U3-SDO{slash}SA0-Pad1)") (class "Default")
      (node (ref "U3") (pin "1") (pinfunction "SDO/SA0_1") (pintype "bidirectional+no_connect"))
    )
  )
)
